# OxyBrain_V1_2.net
KiCad netlist of a schematic drawn in EAGLE
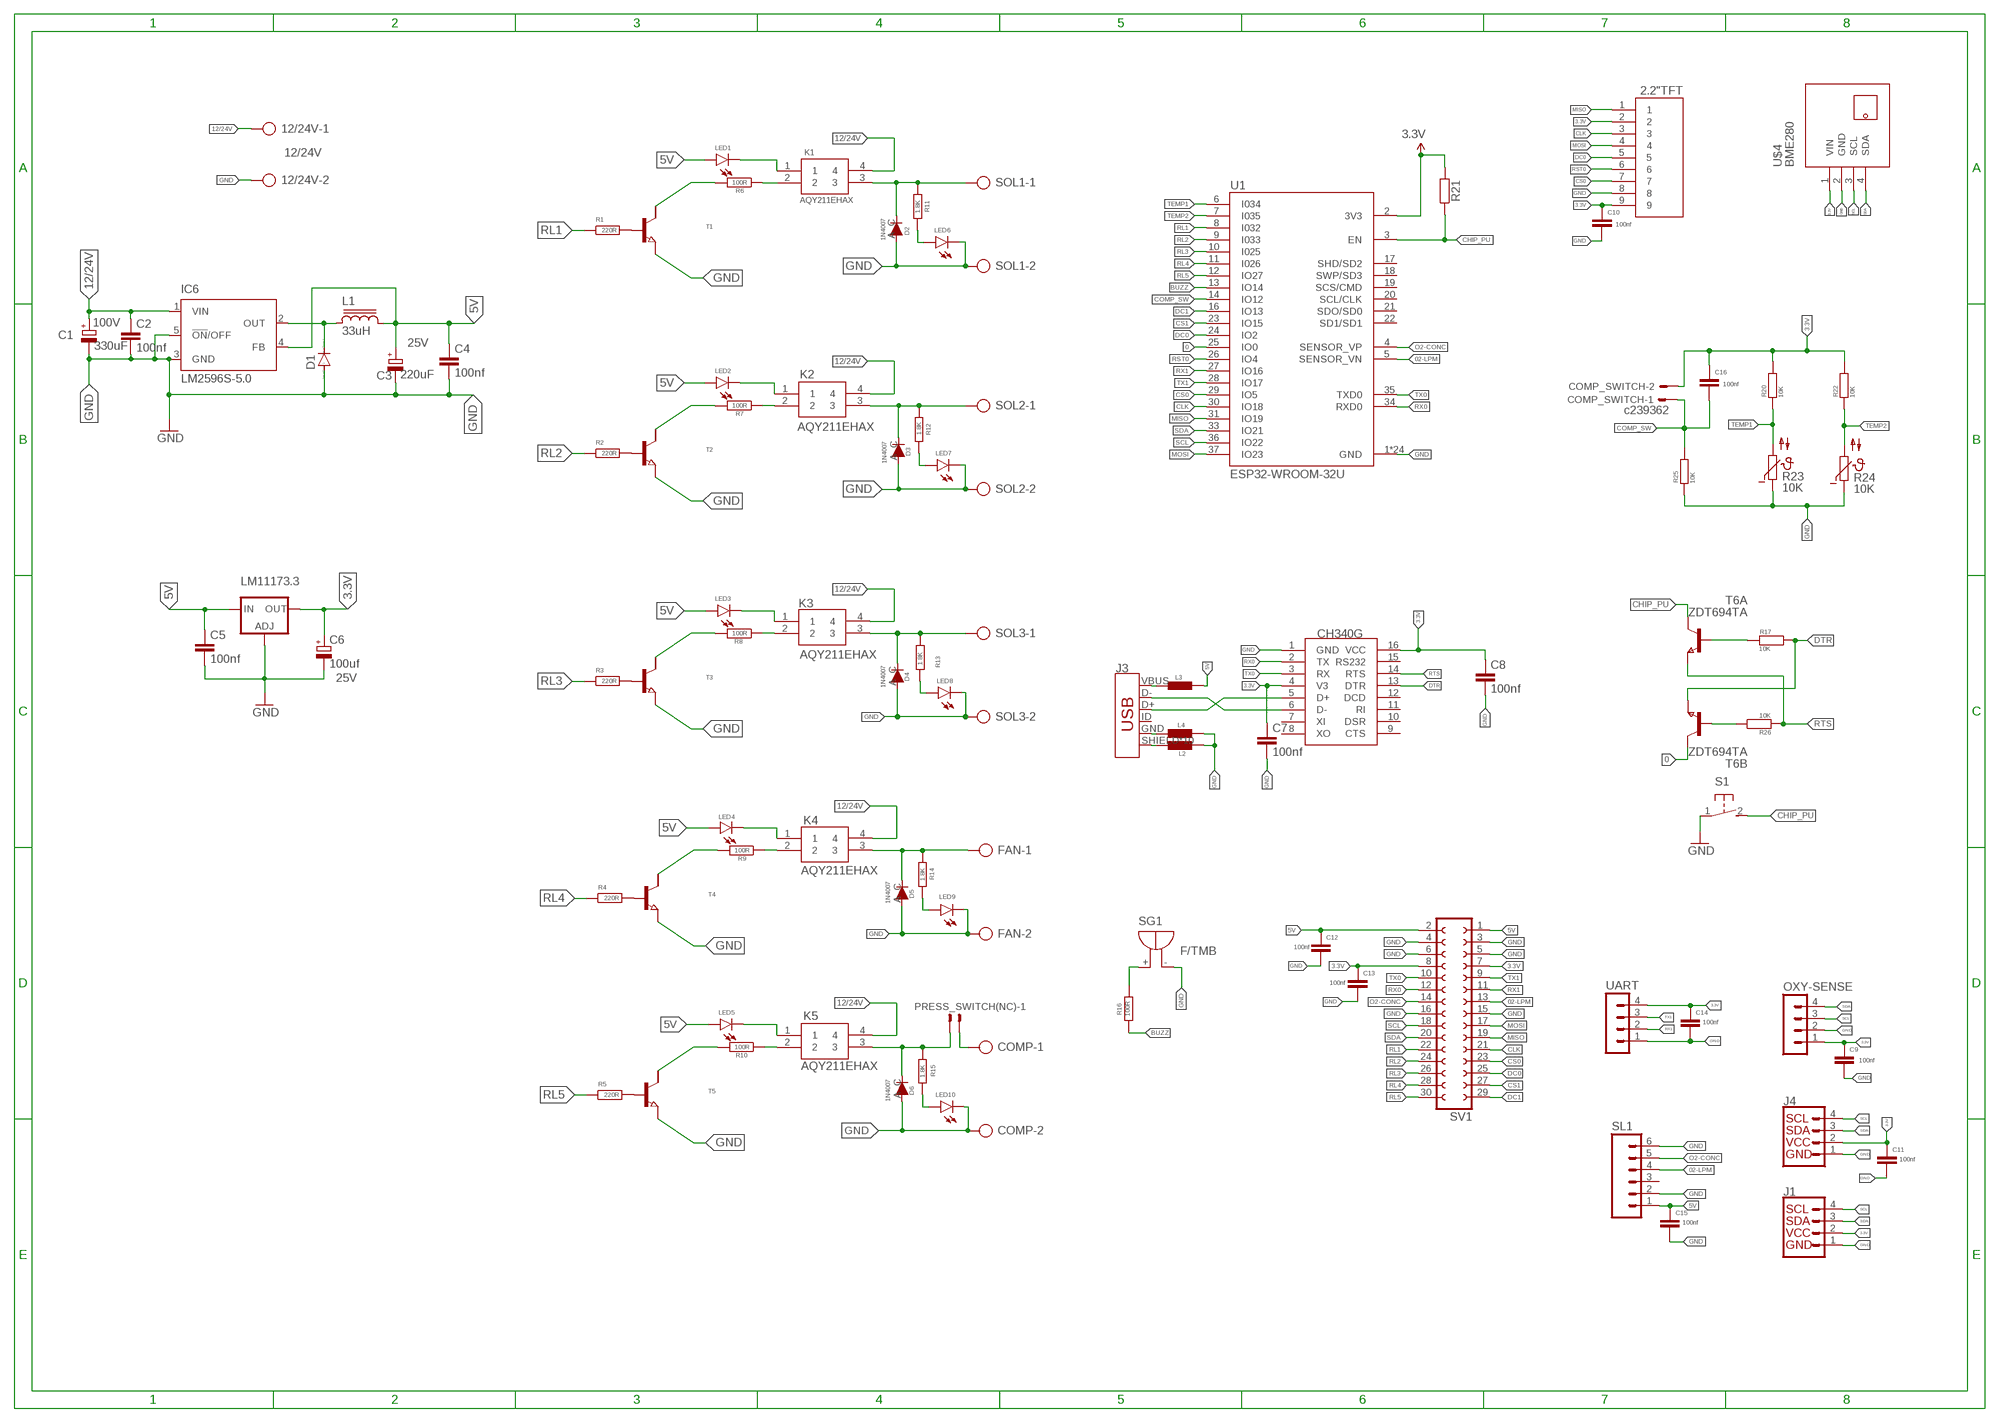
[diagram p0: schematic, sheet 1]

(export (version "E")
  (design (tool "Eeschema 10.0.6"))
  (components
    (comp (ref "2.2\"TFT")
      (value "1735446-9")
      (footprint "eagle-import:SHDR9W60P0X200_1X9_2000X520X63")
      (fields (field (name "MOUSER_PART_NUMBER") "571-1735446-9"))
      (libsource (lib "eagle-import") (part "1735446-9"))
    )
    (comp (ref "12/24V")
      (value "12/24V")
      (footprint "eagle-import:AK500_2")
      (libsource (lib "eagle-import") (part "AK500/2"))
    )
    (comp (ref "C1")
      (value "330uF")
      (footprint "eagle-import:140CLH-1010")
      (fields (field (name "VOLTAGE") "100V"))
      (libsource (lib "eagle-import") (part "CPOL-EU140CLH-1010"))
    )
    (comp (ref "C2")
      (value "100nf")
      (footprint "eagle-import:C1206")
      (libsource (lib "eagle-import") (part "C-EUC1206"))
    )
    (comp (ref "C3")
      (value "220uF")
      (footprint "eagle-import:153CLV-0605")
      (fields (field (name "VOLTAGE") "25V"))
      (libsource (lib "eagle-import") (part "CPOL-EU153CLV-0605"))
    )
    (comp (ref "C4")
      (value "100nf")
      (footprint "eagle-import:C1206")
      (libsource (lib "eagle-import") (part "C-EUC1206"))
    )
    (comp (ref "C5")
      (value "100nf")
      (footprint "eagle-import:C1206")
      (libsource (lib "eagle-import") (part "C-EUC1206"))
    )
    (comp (ref "C6")
      (value "100uf")
      (footprint "eagle-import:153CLV-0605")
      (fields (field (name "VOLTAGE") "25V"))
      (libsource (lib "eagle-import") (part "CPOL-EU153CLV-0605"))
    )
    (comp (ref "C7")
      (value "100nf")
      (footprint "eagle-import:C1206")
      (libsource (lib "eagle-import") (part "C-EUC1206"))
    )
    (comp (ref "C8")
      (value "100nf")
      (footprint "eagle-import:C1206")
      (libsource (lib "eagle-import") (part "C-EUC1206"))
    )
    (comp (ref "C9")
      (value "100nf")
      (footprint "eagle-import:C1206")
      (libsource (lib "eagle-import") (part "C-EUC1206"))
    )
    (comp (ref "C10")
      (value "100nf")
      (footprint "eagle-import:C1206")
      (libsource (lib "eagle-import") (part "C-EUC1206"))
    )
    (comp (ref "C11")
      (value "100nf")
      (footprint "eagle-import:C1206")
      (libsource (lib "eagle-import") (part "C-EUC1206"))
    )
    (comp (ref "C12")
      (value "100nf")
      (footprint "eagle-import:C1206")
      (libsource (lib "eagle-import") (part "C-EUC1206"))
    )
    (comp (ref "C13")
      (value "100nf")
      (footprint "eagle-import:C1206")
      (libsource (lib "eagle-import") (part "C-EUC1206"))
    )
    (comp (ref "C14")
      (value "100nf")
      (footprint "eagle-import:C1206")
      (libsource (lib "eagle-import") (part "C-EUC1206"))
    )
    (comp (ref "C15")
      (value "100nf")
      (footprint "eagle-import:C1206")
      (libsource (lib "eagle-import") (part "C-EUC1206"))
    )
    (comp (ref "C16")
      (value "100nf")
      (footprint "eagle-import:C1206")
      (libsource (lib "eagle-import") (part "C-EUC1206"))
    )
    (comp (ref "COMP")
      (value "AK500/2")
      (footprint "eagle-import:AK500_2")
      (libsource (lib "eagle-import") (part "AK500/2"))
    )
    (comp (ref "COMP_SWITCH")
      (value "c239362")
      (footprint "eagle-import:22-23-2021")
      (fields (field (name "MF") "MOLEX") (field (name "MPN") "22-23-2021"))
      (libsource (lib "eagle-import") (part "22-23-2021"))
    )
    (comp (ref "D1")
      (value "DIODE-SOD123")
      (footprint "eagle-import:SOD123")
      (libsource (lib "eagle-import") (part "DIODE-SOD123"))
    )
    (comp (ref "D2")
      (value "1N4007")
      (footprint "eagle-import:SOD-123FL")
      (libsource (lib "eagle-import") (part "1N4007_SMDSOD123-FL"))
    )
    (comp (ref "D3")
      (value "1N4007")
      (footprint "eagle-import:SOD-123FL")
      (libsource (lib "eagle-import") (part "1N4007_SMDSOD123-FL"))
    )
    (comp (ref "D4")
      (value "1N4007")
      (footprint "eagle-import:SOD-123FL")
      (libsource (lib "eagle-import") (part "1N4007_SMDSOD123-FL"))
    )
    (comp (ref "D5")
      (value "1N4007")
      (footprint "eagle-import:SOD-123FL")
      (libsource (lib "eagle-import") (part "1N4007_SMDSOD123-FL"))
    )
    (comp (ref "D6")
      (value "1N4007")
      (footprint "eagle-import:SOD-123FL")
      (libsource (lib "eagle-import") (part "1N4007_SMDSOD123-FL"))
    )
    (comp (ref "FAN")
      (value "AK500/2")
      (footprint "eagle-import:AK500_2")
      (libsource (lib "eagle-import") (part "AK500/2"))
    )
    (comp (ref "IC6")
      (value "LM2596S-5.0")
      (footprint "eagle-import:TO263-5")
      (fields (field (name "MF") "NATIONAL SEMICONDUCTOR") (field (name "MPN") "LM2596S-ADJ/NOPB"))
      (libsource (lib "eagle-import") (part "LM2596S"))
    )
    (comp (ref "J1")
      (value "I2C_STANDARD")
      (footprint "eagle-import:1X04")
      (libsource (lib "eagle-import") (part "I2C_STANDARD"))
    )
    (comp (ref "J3")
      (value "USB_MICRO-B_HALF_PTH_MILL")
      (footprint "eagle-import:USB-MICROB-PTH-MILL")
      (libsource (lib "eagle-import") (part "USB_MICRO-B_HALF_PTH_MILL"))
    )
    (comp (ref "J4")
      (value "I2C_STANDARD")
      (footprint "eagle-import:1X04")
      (libsource (lib "eagle-import") (part "I2C_STANDARD"))
    )
    (comp (ref "K1")
      (value "AQY211EHAX")
      (footprint "eagle-import:AQY21(SMD_DIP)")
      (fields (field (name "MOUSER_PART_NUMBER") "769-AQY211EHAX"))
      (libsource (lib "eagle-import") (part "AQY211EHAX"))
    )
    (comp (ref "K2")
      (value "AQY211EHAX")
      (footprint "eagle-import:AQY21(SMD_DIP)")
      (fields (field (name "MOUSER_PART_NUMBER") "769-AQY211EHAX"))
      (libsource (lib "eagle-import") (part "AQY211EHAX"))
    )
    (comp (ref "K3")
      (value "AQY211EHAX")
      (footprint "eagle-import:AQY21(SMD_DIP)")
      (fields (field (name "MOUSER_PART_NUMBER") "769-AQY211EHAX"))
      (libsource (lib "eagle-import") (part "AQY211EHAX"))
    )
    (comp (ref "K4")
      (value "AQY211EHAX")
      (footprint "eagle-import:AQY21(SMD_DIP)")
      (fields (field (name "MOUSER_PART_NUMBER") "769-AQY211EHAX"))
      (libsource (lib "eagle-import") (part "AQY211EHAX"))
    )
    (comp (ref "K5")
      (value "AQY211EHAX")
      (footprint "eagle-import:AQY21(SMD_DIP)")
      (fields (field (name "MOUSER_PART_NUMBER") "769-AQY211EHAX"))
      (libsource (lib "eagle-import") (part "AQY211EHAX"))
    )
    (comp (ref "L1")
      (value "33uH")
      (footprint "eagle-import:CDRH127_LD")
      (libsource (lib "eagle-import") (part "CDRH127/LD"))
    )
    (comp (ref "L2")
      (value "BLM15HD102SN1")
      (footprint "eagle-import:0402")
      (libsource (lib "eagle-import") (part "BLM15HD102SN1"))
    )
    (comp (ref "L3")
      (value "BLM15HD102SN1")
      (footprint "eagle-import:0402")
      (libsource (lib "eagle-import") (part "BLM15HD102SN1"))
    )
    (comp (ref "L4")
      (value "BLM15HD102SN1")
      (footprint "eagle-import:0402")
      (libsource (lib "eagle-import") (part "BLM15HD102SN1"))
    )
    (comp (ref "LED1")
      (value "LEDCHIPLED_1206")
      (footprint "eagle-import:CHIPLED_1206")
      (libsource (lib "eagle-import") (part "LEDCHIPLED_1206"))
    )
    (comp (ref "LED2")
      (value "LEDCHIPLED_1206")
      (footprint "eagle-import:CHIPLED_1206")
      (libsource (lib "eagle-import") (part "LEDCHIPLED_1206"))
    )
    (comp (ref "LED3")
      (value "LEDCHIPLED_1206")
      (footprint "eagle-import:CHIPLED_1206")
      (libsource (lib "eagle-import") (part "LEDCHIPLED_1206"))
    )
    (comp (ref "LED4")
      (value "LEDCHIPLED_1206")
      (footprint "eagle-import:CHIPLED_1206")
      (libsource (lib "eagle-import") (part "LEDCHIPLED_1206"))
    )
    (comp (ref "LED5")
      (value "LEDCHIPLED_1206")
      (footprint "eagle-import:CHIPLED_1206")
      (libsource (lib "eagle-import") (part "LEDCHIPLED_1206"))
    )
    (comp (ref "LED6")
      (value "LEDCHIPLED_1206")
      (footprint "eagle-import:CHIPLED_1206")
      (libsource (lib "eagle-import") (part "LEDCHIPLED_1206"))
    )
    (comp (ref "LED7")
      (value "LEDCHIPLED_1206")
      (footprint "eagle-import:CHIPLED_1206")
      (libsource (lib "eagle-import") (part "LEDCHIPLED_1206"))
    )
    (comp (ref "LED8")
      (value "LEDCHIPLED_1206")
      (footprint "eagle-import:CHIPLED_1206")
      (libsource (lib "eagle-import") (part "LEDCHIPLED_1206"))
    )
    (comp (ref "LED9")
      (value "LEDCHIPLED_1206")
      (footprint "eagle-import:CHIPLED_1206")
      (libsource (lib "eagle-import") (part "LEDCHIPLED_1206"))
    )
    (comp (ref "LED10")
      (value "LEDCHIPLED_1206")
      (footprint "eagle-import:CHIPLED_1206")
      (libsource (lib "eagle-import") (part "LEDCHIPLED_1206"))
    )
    (comp (ref "LM11173.3")
      (value "LD117ADT33TR")
      (footprint "eagle-import:DPACK")
      (libsource (lib "eagle-import") (part "LD117A?DT33TR"))
    )
    (comp (ref "OXY-SENSE")
      (value "MA04-1")
      (footprint "eagle-import:MA04-1")
      (libsource (lib "eagle-import") (part "MA04-1"))
    )
    (comp (ref "PRESS_SWITCH(NC)")
      (value "c239362")
      (footprint "eagle-import:22-23-2021")
      (fields (field (name "MF") "MOLEX") (field (name "MPN") "22-23-2021"))
      (libsource (lib "eagle-import") (part "22-23-2021"))
    )
    (comp (ref "R1")
      (value "220R")
      (footprint "eagle-import:M1206")
      (libsource (lib "eagle-import") (part "R-EU_M1206"))
    )
    (comp (ref "R2")
      (value "220R")
      (footprint "eagle-import:M1206")
      (libsource (lib "eagle-import") (part "R-EU_M1206"))
    )
    (comp (ref "R3")
      (value "220R")
      (footprint "eagle-import:M1206")
      (libsource (lib "eagle-import") (part "R-EU_M1206"))
    )
    (comp (ref "R4")
      (value "220R")
      (footprint "eagle-import:M1206")
      (libsource (lib "eagle-import") (part "R-EU_M1206"))
    )
    (comp (ref "R5")
      (value "220R")
      (footprint "eagle-import:M1206")
      (libsource (lib "eagle-import") (part "R-EU_M1206"))
    )
    (comp (ref "R6")
      (value "100R")
      (footprint "eagle-import:M1206")
      (libsource (lib "eagle-import") (part "R-EU_M1206"))
    )
    (comp (ref "R7")
      (value "100R")
      (footprint "eagle-import:M1206")
      (libsource (lib "eagle-import") (part "R-EU_M1206"))
    )
    (comp (ref "R8")
      (value "100R")
      (footprint "eagle-import:M1206")
      (libsource (lib "eagle-import") (part "R-EU_M1206"))
    )
    (comp (ref "R9")
      (value "100R")
      (footprint "eagle-import:M1206")
      (libsource (lib "eagle-import") (part "R-EU_M1206"))
    )
    (comp (ref "R10")
      (value "100R")
      (footprint "eagle-import:M1206")
      (libsource (lib "eagle-import") (part "R-EU_M1206"))
    )
    (comp (ref "R11")
      (value "1.8K")
      (footprint "eagle-import:M1206")
      (libsource (lib "eagle-import") (part "R-EU_M1206"))
    )
    (comp (ref "R12")
      (value "1.8K")
      (footprint "eagle-import:M1206")
      (libsource (lib "eagle-import") (part "R-EU_M1206"))
    )
    (comp (ref "R13")
      (value "1.8K")
      (footprint "eagle-import:M1206")
      (libsource (lib "eagle-import") (part "R-EU_M1206"))
    )
    (comp (ref "R14")
      (value "1.8K")
      (footprint "eagle-import:M1206")
      (libsource (lib "eagle-import") (part "R-EU_M1206"))
    )
    (comp (ref "R15")
      (value "1.8K")
      (footprint "eagle-import:M1206")
      (libsource (lib "eagle-import") (part "R-EU_M1206"))
    )
    (comp (ref "R16")
      (value "100R")
      (footprint "eagle-import:M1206")
      (libsource (lib "eagle-import") (part "R-EU_M1206"))
    )
    (comp (ref "R17")
      (value "10K")
      (footprint "eagle-import:M1206")
      (libsource (lib "eagle-import") (part "R-EU_M1206"))
    )
    (comp (ref "R20")
      (value "10K")
      (footprint "eagle-import:M1206")
      (libsource (lib "eagle-import") (part "R-EU_M1206"))
    )
    (comp (ref "R21")
      (value "10k")
      (footprint "eagle-import:M1206")
      (libsource (lib "eagle-import") (part "R-EU_M1206"))
    )
    (comp (ref "R22")
      (value "10K")
      (footprint "eagle-import:M1206")
      (libsource (lib "eagle-import") (part "R-EU_M1206"))
    )
    (comp (ref "R23")
      (value "10K")
      (footprint "eagle-import:P640")
      (libsource (lib "eagle-import") (part "NTC640"))
    )
    (comp (ref "R24")
      (value "10K")
      (footprint "eagle-import:P640")
      (libsource (lib "eagle-import") (part "NTC640"))
    )
    (comp (ref "R25")
      (value "10K")
      (footprint "eagle-import:M1206")
      (libsource (lib "eagle-import") (part "R-EU_M1206"))
    )
    (comp (ref "R26")
      (value "10K")
      (footprint "eagle-import:M1206")
      (libsource (lib "eagle-import") (part "R-EU_M1206"))
    )
    (comp (ref "S1")
      (value "B3U-1000P(M)-B")
      (footprint "eagle-import:DTSM-3")
      (libsource (lib "eagle-import") (part "DTSM-3"))
    )
    (comp (ref "SG1")
      (value "F/TMB")
      (footprint "eagle-import:F_TMB")
      (libsource (lib "eagle-import") (part "F/TMB"))
    )
    (comp (ref "SL1")
      (value "M06")
      (footprint "eagle-import:06P")
      (libsource (lib "eagle-import") (part "M06"))
    )
    (comp (ref "SOL1")
      (value "AK500/2")
      (footprint "eagle-import:AK500_2")
      (libsource (lib "eagle-import") (part "AK500/2"))
    )
    (comp (ref "SOL2")
      (value "AK500/2")
      (footprint "eagle-import:AK500_2")
      (libsource (lib "eagle-import") (part "AK500/2"))
    )
    (comp (ref "SOL3")
      (value "AK500/2")
      (footprint "eagle-import:AK500_2")
      (libsource (lib "eagle-import") (part "AK500/2"))
    )
    (comp (ref "SV1")
      (value "FE15-2")
      (footprint "eagle-import:FE15-2")
      (libsource (lib "eagle-import") (part "FE15-2"))
    )
    (comp (ref "T1")
      (value "600mA/40V")
      (footprint "eagle-import:SOT89")
      (libsource (lib "eagle-import") (part "NPN-TRANSISTIOR-2COLSOT89"))
    )
    (comp (ref "T2")
      (value "600mA/40V")
      (footprint "eagle-import:SOT89")
      (libsource (lib "eagle-import") (part "NPN-TRANSISTIOR-2COLSOT89"))
    )
    (comp (ref "T3")
      (value "600mA/40V")
      (footprint "eagle-import:SOT89")
      (libsource (lib "eagle-import") (part "NPN-TRANSISTIOR-2COLSOT89"))
    )
    (comp (ref "T4")
      (value "600mA/40V")
      (footprint "eagle-import:SOT89")
      (libsource (lib "eagle-import") (part "NPN-TRANSISTIOR-2COLSOT89"))
    )
    (comp (ref "T5")
      (value "600mA/40V")
      (footprint "eagle-import:SOT89")
      (libsource (lib "eagle-import") (part "NPN-TRANSISTIOR-2COLSOT89"))
    )
    (comp (ref "T6")
      (value "ZDT694TA")
      (footprint "eagle-import:SM8")
      (libsource (lib "eagle-import") (part "NPN2SM8"))
    )
    (comp (ref "U$1")
      (value "CH340G")
      (footprint "eagle-import:SOIC16")
      (libsource (lib "eagle-import") (part "CH340G"))
    )
    (comp (ref "U$4")
      (value "BME280")
      (footprint "eagle-import:TEMP-HUM-PRES-BME280")
      (libsource (lib "eagle-import") (part "TEMP-HUM-PRES-BME280"))
    )
    (comp (ref "U1")
      (value "ESP32-WROOM-32U")
      (footprint "eagle-import:XCVR_ESP32-WROOM-32U")
      (fields (field (name "MF") "Espressif Systems"))
      (libsource (lib "eagle-import") (part "ESP32-WROOM-32U"))
    )
    (comp (ref "UART")
      (value "MA04-1")
      (footprint "eagle-import:MA04-1")
      (libsource (lib "eagle-import") (part "MA04-1"))
    )
  )
  (nets
    (net (code "1") (name "0") (class "Default")
      (node (ref "T6") (pin "7") (pinfunction "C_7") (pintype "passive"))
      (node (ref "T6") (pin "8") (pinfunction "C_8") (pintype "passive"))
      (node (ref "U1") (pin "25") (pinfunction "IO0_25") (pintype "bidirectional"))
    )
    (net (code "2") (name "02-LPM") (class "Default")
      (node (ref "SL1") (pin "4") (pinfunction "4_4") (pintype "passive"))
      (node (ref "SV1") (pin "13") (pinfunction "13_13") (pintype "passive"))
      (node (ref "U1") (pin "5") (pinfunction "SENSOR_VN_5") (pintype "input"))
    )
    (net (code "3") (name "3.3V") (class "Default")
      (node (ref "2.2\"TFT") (pin "2") (pinfunction "2_2") (pintype "bidirectional"))
      (node (ref "2.2\"TFT") (pin "9") (pinfunction "9_9") (pintype "bidirectional"))
      (node (ref "C10") (pin "1") (pinfunction "1_1") (pintype "passive"))
      (node (ref "C11") (pin "1") (pinfunction "1_1") (pintype "passive"))
      (node (ref "C13") (pin "1") (pinfunction "1_1") (pintype "passive"))
      (node (ref "C14") (pin "1") (pinfunction "1_1") (pintype "passive"))
      (node (ref "C16") (pin "1") (pinfunction "1_1") (pintype "passive"))
      (node (ref "C6") (pin "+") (pinfunction "+_+") (pintype "passive"))
      (node (ref "C7") (pin "1") (pinfunction "1_1") (pintype "passive"))
      (node (ref "C8") (pin "1") (pinfunction "1_1") (pintype "passive"))
      (node (ref "C9") (pin "1") (pinfunction "1_1") (pintype "passive"))
      (node (ref "COMP_SWITCH") (pin "2") (pinfunction "S_2") (pintype "passive"))
      (node (ref "J1") (pin "2") (pinfunction "2_2") (pintype "power_in"))
      (node (ref "J4") (pin "2") (pinfunction "2_2") (pintype "power_in"))
      (node (ref "LM11173.3") (pin "4") (pinfunction "OUT_4") (pintype "passive"))
      (node (ref "OXY-SENSE") (pin "1") (pinfunction "1_1") (pintype "passive"))
      (node (ref "R20") (pin "1") (pinfunction "1_1") (pintype "passive"))
      (node (ref "R21") (pin "2") (pinfunction "2_2") (pintype "passive"))
      (node (ref "R22") (pin "1") (pinfunction "1_1") (pintype "passive"))
      (node (ref "SV1") (pin "7") (pinfunction "7_7") (pintype "passive"))
      (node (ref "SV1") (pin "8") (pinfunction "8_8") (pintype "passive"))
      (node (ref "U$1") (pin "16") (pinfunction "VCC_16") (pintype "bidirectional"))
      (node (ref "U$1") (pin "4") (pinfunction "V3_4") (pintype "bidirectional"))
      (node (ref "U$4") (pin "1") (pinfunction "VIN_1") (pintype "power_in"))
      (node (ref "U1") (pin "2") (pinfunction "3V3_2") (pintype "power_in"))
      (node (ref "UART") (pin "4") (pinfunction "4_4") (pintype "passive"))
    )
    (net (code "4") (name "5V") (class "Default")
      (node (ref "C12") (pin "1") (pinfunction "1_1") (pintype "passive"))
      (node (ref "C15") (pin "1") (pinfunction "1_1") (pintype "passive"))
      (node (ref "C3") (pin "+") (pinfunction "+_+") (pintype "passive"))
      (node (ref "C4") (pin "1") (pinfunction "1_1") (pintype "passive"))
      (node (ref "C5") (pin "1") (pinfunction "1_1") (pintype "passive"))
      (node (ref "IC6") (pin "4") (pinfunction "FB_4") (pintype "input"))
      (node (ref "L1") (pin "2") (pinfunction "2_2") (pintype "passive"))
      (node (ref "L3") (pin "2") (pinfunction "2_2") (pintype "passive"))
      (node (ref "LED1") (pin "A") (pinfunction "A_A") (pintype "passive"))
      (node (ref "LED2") (pin "A") (pinfunction "A_A") (pintype "passive"))
      (node (ref "LED3") (pin "A") (pinfunction "A_A") (pintype "passive"))
      (node (ref "LED4") (pin "A") (pinfunction "A_A") (pintype "passive"))
      (node (ref "LED5") (pin "A") (pinfunction "A_A") (pintype "passive"))
      (node (ref "LM11173.3") (pin "3") (pinfunction "IN_3") (pintype "input"))
      (node (ref "SL1") (pin "1") (pinfunction "1_1") (pintype "passive"))
      (node (ref "SV1") (pin "1") (pinfunction "1_1") (pintype "passive"))
      (node (ref "SV1") (pin "2") (pinfunction "2_2") (pintype "passive"))
    )
    (net (code "5") (name "12{slash}24V") (class "Default")
      (node (ref "12/24V") (pin "1") (pinfunction "KL_1") (pintype "passive"))
      (node (ref "C1") (pin "+") (pinfunction "+_+") (pintype "passive"))
      (node (ref "C2") (pin "1") (pinfunction "1_1") (pintype "passive"))
      (node (ref "IC6") (pin "1") (pinfunction "VIN_1") (pintype "input"))
      (node (ref "K1") (pin "4") (pinfunction "4_4") (pintype "bidirectional"))
      (node (ref "K2") (pin "4") (pinfunction "4_4") (pintype "bidirectional"))
      (node (ref "K3") (pin "4") (pinfunction "4_4") (pintype "bidirectional"))
      (node (ref "K4") (pin "4") (pinfunction "4_4") (pintype "bidirectional"))
      (node (ref "K5") (pin "4") (pinfunction "4_4") (pintype "bidirectional"))
    )
    (net (code "6") (name "BUZZ") (class "Default")
      (node (ref "R16") (pin "1") (pinfunction "1_1") (pintype "passive"))
      (node (ref "U1") (pin "13") (pinfunction "IO14_13") (pintype "bidirectional"))
    )
    (net (code "7") (name "CHIP_PU") (class "Default")
      (node (ref "R21") (pin "1") (pinfunction "1_1") (pintype "passive"))
      (node (ref "S1") (pin "2") (pinfunction "2_2") (pintype "passive"))
      (node (ref "T6") (pin "5") (pinfunction "C_5") (pintype "passive"))
      (node (ref "T6") (pin "6") (pinfunction "C_6") (pintype "passive"))
      (node (ref "U1") (pin "3") (pinfunction "EN_3") (pintype "input"))
    )
    (net (code "8") (name "CLK") (class "Default")
      (node (ref "2.2\"TFT") (pin "3") (pinfunction "3_3") (pintype "bidirectional"))
      (node (ref "SV1") (pin "21") (pinfunction "21_21") (pintype "passive"))
      (node (ref "U1") (pin "30") (pinfunction "IO18_30") (pintype "bidirectional"))
    )
    (net (code "9") (name "COMP_SW") (class "Default")
      (node (ref "C16") (pin "2") (pinfunction "2_2") (pintype "passive"))
      (node (ref "COMP_SWITCH") (pin "1") (pinfunction "S_1") (pintype "passive"))
      (node (ref "R25") (pin "1") (pinfunction "1_1") (pintype "passive"))
      (node (ref "U1") (pin "14") (pinfunction "IO12_14") (pintype "bidirectional"))
    )
    (net (code "10") (name "CS0") (class "Default")
      (node (ref "2.2\"TFT") (pin "7") (pinfunction "7_7") (pintype "bidirectional"))
      (node (ref "SV1") (pin "23") (pinfunction "23_23") (pintype "passive"))
      (node (ref "U1") (pin "29") (pinfunction "IO5_29") (pintype "bidirectional"))
    )
    (net (code "11") (name "CS1") (class "Default")
      (node (ref "SV1") (pin "27") (pinfunction "27_27") (pintype "passive"))
      (node (ref "U1") (pin "23") (pinfunction "IO15_23") (pintype "bidirectional"))
    )
    (net (code "12") (name "DC0") (class "Default")
      (node (ref "2.2\"TFT") (pin "5") (pinfunction "5_5") (pintype "bidirectional"))
      (node (ref "SV1") (pin "25") (pinfunction "25_25") (pintype "passive"))
      (node (ref "U1") (pin "24") (pinfunction "IO2_24") (pintype "bidirectional"))
    )
    (net (code "13") (name "DC1") (class "Default")
      (node (ref "SV1") (pin "29") (pinfunction "29_29") (pintype "passive"))
      (node (ref "U1") (pin "16") (pinfunction "IO13_16") (pintype "bidirectional"))
    )
    (net (code "14") (name "DTR") (class "Default")
      (node (ref "R17") (pin "1") (pinfunction "1_1") (pintype "passive"))
      (node (ref "T6") (pin "1") (pinfunction "E_1") (pintype "passive"))
      (node (ref "U$1") (pin "13") (pinfunction "DTR_13") (pintype "bidirectional"))
    )
    (net (code "15") (name "GND") (class "Default")
      (node (ref "12/24V") (pin "2") (pinfunction "KL_2") (pintype "passive"))
      (node (ref "2.2\"TFT") (pin "8") (pinfunction "8_8") (pintype "bidirectional"))
      (node (ref "C1") (pin "-") (pinfunction "-_-") (pintype "passive"))
      (node (ref "C10") (pin "2") (pinfunction "2_2") (pintype "passive"))
      (node (ref "C11") (pin "2") (pinfunction "2_2") (pintype "passive"))
      (node (ref "C12") (pin "2") (pinfunction "2_2") (pintype "passive"))
      (node (ref "C13") (pin "2") (pinfunction "2_2") (pintype "passive"))
      (node (ref "C14") (pin "2") (pinfunction "2_2") (pintype "passive"))
      (node (ref "C15") (pin "2") (pinfunction "2_2") (pintype "passive"))
      (node (ref "C2") (pin "2") (pinfunction "2_2") (pintype "passive"))
      (node (ref "C3") (pin "-") (pinfunction "-_-") (pintype "passive"))
      (node (ref "C4") (pin "2") (pinfunction "2_2") (pintype "passive"))
      (node (ref "C5") (pin "2") (pinfunction "2_2") (pintype "passive"))
      (node (ref "C6") (pin "-") (pinfunction "-_-") (pintype "passive"))
      (node (ref "C7") (pin "2") (pinfunction "2_2") (pintype "passive"))
      (node (ref "C8") (pin "2") (pinfunction "2_2") (pintype "passive"))
      (node (ref "C9") (pin "2") (pinfunction "2_2") (pintype "passive"))
      (node (ref "COMP") (pin "2") (pinfunction "KL_2") (pintype "passive"))
      (node (ref "D1") (pin "A") (pinfunction "A_A") (pintype "passive"))
      (node (ref "D2") (pin "A") (pinfunction "A_A") (pintype "bidirectional"))
      (node (ref "D3") (pin "A") (pinfunction "A_A") (pintype "bidirectional"))
      (node (ref "D4") (pin "A") (pinfunction "A_A") (pintype "bidirectional"))
      (node (ref "D5") (pin "A") (pinfunction "A_A") (pintype "bidirectional"))
      (node (ref "D6") (pin "A") (pinfunction "A_A") (pintype "bidirectional"))
      (node (ref "FAN") (pin "2") (pinfunction "KL_2") (pintype "passive"))
      (node (ref "IC6") (pin "3") (pinfunction "GND_3") (pintype "power_in"))
      (node (ref "IC6") (pin "5") (pinfunction "~{ON}/OFF_5") (pintype "input"))
      (node (ref "J1") (pin "1") (pinfunction "1_1") (pintype "power_in"))
      (node (ref "J4") (pin "1") (pinfunction "1_1") (pintype "power_in"))
      (node (ref "L2") (pin "2") (pinfunction "2_2") (pintype "passive"))
      (node (ref "L4") (pin "2") (pinfunction "2_2") (pintype "passive"))
      (node (ref "LED10") (pin "C") (pinfunction "C_C") (pintype "passive"))
      (node (ref "LED6") (pin "C") (pinfunction "C_C") (pintype "passive"))
      (node (ref "LED7") (pin "C") (pinfunction "C_C") (pintype "passive"))
      (node (ref "LED8") (pin "C") (pinfunction "C_C") (pintype "passive"))
      (node (ref "LED9") (pin "C") (pinfunction "C_C") (pintype "passive"))
      (node (ref "LM11173.3") (pin "1") (pinfunction "ADJ_1") (pintype "input"))
      (node (ref "OXY-SENSE") (pin "2") (pinfunction "2_2") (pintype "passive"))
      (node (ref "R23") (pin "1") (pinfunction "1_1") (pintype "passive"))
      (node (ref "R24") (pin "1") (pinfunction "1_1") (pintype "passive"))
      (node (ref "R25") (pin "2") (pinfunction "2_2") (pintype "passive"))
      (node (ref "S1") (pin "1") (pinfunction "1_1") (pintype "passive"))
      (node (ref "SG1") (pin "-") (pinfunction "-_-") (pintype "passive"))
      (node (ref "SL1") (pin "2") (pinfunction "2_2") (pintype "passive"))
      (node (ref "SL1") (pin "6") (pinfunction "6_6") (pintype "passive"))
      (node (ref "SOL1") (pin "2") (pinfunction "KL_2") (pintype "passive"))
      (node (ref "SOL2") (pin "2") (pinfunction "KL_2") (pintype "passive"))
      (node (ref "SOL3") (pin "2") (pinfunction "KL_2") (pintype "passive"))
      (node (ref "SV1") (pin "15") (pinfunction "15_15") (pintype "passive"))
      (node (ref "SV1") (pin "16") (pinfunction "16_16") (pintype "passive"))
      (node (ref "SV1") (pin "3") (pinfunction "3_3") (pintype "passive"))
      (node (ref "SV1") (pin "4") (pinfunction "4_4") (pintype "passive"))
      (node (ref "SV1") (pin "5") (pinfunction "5_5") (pintype "passive"))
      (node (ref "SV1") (pin "6") (pinfunction "6_6") (pintype "passive"))
      (node (ref "T1") (pin "3") (pinfunction "E_3") (pintype "passive"))
      (node (ref "T2") (pin "3") (pinfunction "E_3") (pintype "passive"))
      (node (ref "T3") (pin "3") (pinfunction "E_3") (pintype "passive"))
      (node (ref "T4") (pin "3") (pinfunction "E_3") (pintype "passive"))
      (node (ref "T5") (pin "3") (pinfunction "E_3") (pintype "passive"))
      (node (ref "U$1") (pin "1") (pinfunction "GND_1") (pintype "bidirectional"))
      (node (ref "U$4") (pin "2") (pinfunction "GND_2") (pintype "power_in"))
      (node (ref "U1") (pin "1") (pinfunction "GND_1") (pintype "power_in"))
      (node (ref "U1") (pin "15") (pinfunction "GND_15") (pintype "power_in"))
      (node (ref "U1") (pin "38") (pinfunction "GND_38") (pintype "power_in"))
      (node (ref "U1") (pin "G.1") (pinfunction "GND_G.1") (pintype "power_in"))
      (node (ref "U1") (pin "G.10") (pinfunction "GND_G.10") (pintype "power_in"))
      (node (ref "U1") (pin "G.11") (pinfunction "GND_G.11") (pintype "power_in"))
      (node (ref "U1") (pin "G.12") (pinfunction "GND_G.12") (pintype "power_in"))
      (node (ref "U1") (pin "G.13") (pinfunction "GND_G.13") (pintype "power_in"))
      (node (ref "U1") (pin "G.14") (pinfunction "GND_G.14") (pintype "power_in"))
      (node (ref "U1") (pin "G.15") (pinfunction "GND_G.15") (pintype "power_in"))
      (node (ref "U1") (pin "G.16") (pinfunction "GND_G.16") (pintype "power_in"))
      (node (ref "U1") (pin "G.17") (pinfunction "GND_G.17") (pintype "power_in"))
      (node (ref "U1") (pin "G.18") (pinfunction "GND_G.18") (pintype "power_in"))
      (node (ref "U1") (pin "G.19") (pinfunction "GND_G.19") (pintype "power_in"))
      (node (ref "U1") (pin "G.2") (pinfunction "GND_G.2") (pintype "power_in"))
      (node (ref "U1") (pin "G.20") (pinfunction "GND_G.20") (pintype "power_in"))
      (node (ref "U1") (pin "G.21") (pinfunction "GND_G.21") (pintype "power_in"))
      (node (ref "U1") (pin "G.22") (pinfunction "GND_G.22") (pintype "power_in"))
      (node (ref "U1") (pin "G.4") (pinfunction "GND_G.4") (pintype "power_in"))
      (node (ref "U1") (pin "G.5") (pinfunction "GND_G.5") (pintype "power_in"))
      (node (ref "U1") (pin "G.6") (pinfunction "GND_G.6") (pintype "power_in"))
      (node (ref "U1") (pin "G.7") (pinfunction "GND_G.7") (pintype "power_in"))
      (node (ref "U1") (pin "G.8") (pinfunction "GND_G.8") (pintype "power_in"))
      (node (ref "U1") (pin "G.9") (pinfunction "GND_G.9") (pintype "power_in"))
      (node (ref "UART") (pin "1") (pinfunction "1_1") (pintype "passive"))
    )
    (net (code "16") (name "MISO") (class "Default")
      (node (ref "2.2\"TFT") (pin "1") (pinfunction "1_1") (pintype "bidirectional"))
      (node (ref "SV1") (pin "19") (pinfunction "19_19") (pintype "passive"))
      (node (ref "U1") (pin "31") (pinfunction "IO19_31") (pintype "bidirectional"))
    )
    (net (code "17") (name "MOSI") (class "Default")
      (node (ref "2.2\"TFT") (pin "4") (pinfunction "4_4") (pintype "bidirectional"))
      (node (ref "SV1") (pin "17") (pinfunction "17_17") (pintype "passive"))
      (node (ref "U1") (pin "37") (pinfunction "IO23_37") (pintype "bidirectional"))
    )
    (net (code "18") (name "Net-(COMPA-KL)") (class "Default")
      (node (ref "COMP") (pin "1") (pinfunction "KL_1") (pintype "passive"))
      (node (ref "PRESS_SWITCH(NC)") (pin "2") (pinfunction "S_2") (pintype "passive"))
    )
    (net (code "19") (name "Net-(D2-K)") (class "Default")
      (node (ref "D2") (pin "C") (pinfunction "K_C") (pintype "bidirectional"))
      (node (ref "K1") (pin "3") (pinfunction "3_3") (pintype "bidirectional"))
      (node (ref "R11") (pin "1") (pinfunction "1_1") (pintype "passive"))
      (node (ref "SOL1") (pin "1") (pinfunction "KL_1") (pintype "passive"))
    )
    (net (code "20") (name "Net-(D3-K)") (class "Default")
      (node (ref "D3") (pin "C") (pinfunction "K_C") (pintype "bidirectional"))
      (node (ref "K2") (pin "3") (pinfunction "3_3") (pintype "bidirectional"))
      (node (ref "R12") (pin "1") (pinfunction "1_1") (pintype "passive"))
      (node (ref "SOL2") (pin "1") (pinfunction "KL_1") (pintype "passive"))
    )
    (net (code "21") (name "Net-(D4-K)") (class "Default")
      (node (ref "D4") (pin "C") (pinfunction "K_C") (pintype "bidirectional"))
      (node (ref "K3") (pin "3") (pinfunction "3_3") (pintype "bidirectional"))
      (node (ref "R13") (pin "1") (pinfunction "1_1") (pintype "passive"))
      (node (ref "SOL3") (pin "1") (pinfunction "KL_1") (pintype "passive"))
    )
    (net (code "22") (name "Net-(D5-K)") (class "Default")
      (node (ref "D5") (pin "C") (pinfunction "K_C") (pintype "bidirectional"))
      (node (ref "FAN") (pin "1") (pinfunction "KL_1") (pintype "passive"))
      (node (ref "K4") (pin "3") (pinfunction "3_3") (pintype "bidirectional"))
      (node (ref "R14") (pin "1") (pinfunction "1_1") (pintype "passive"))
    )
    (net (code "23") (name "Net-(D6-K)") (class "Default")
      (node (ref "D6") (pin "C") (pinfunction "K_C") (pintype "bidirectional"))
      (node (ref "K5") (pin "3") (pinfunction "3_3") (pintype "bidirectional"))
      (node (ref "PRESS_SWITCH(NC)") (pin "1") (pinfunction "S_1") (pintype "passive"))
      (node (ref "R15") (pin "1") (pinfunction "1_1") (pintype "passive"))
    )
    (net (code "24") (name "Net-(IC6-OUT)") (class "Default")
      (node (ref "D1") (pin "C") (pinfunction "C_C") (pintype "passive"))
      (node (ref "IC6") (pin "2") (pinfunction "OUT_2") (pintype "output"))
      (node (ref "L1") (pin "1") (pinfunction "1_1") (pintype "passive"))
    )
    (net (code "25") (name "Net-(J3-PadGND)") (class "Default")
      (node (ref "J3") (pin "GND") (pinfunction "GND_GND") (pintype "power_in"))
      (node (ref "L4") (pin "1") (pinfunction "1_1") (pintype "passive"))
    )
    (net (code "26") (name "Net-(J3-PadSHIELD)") (class "Default")
      (node (ref "J3") (pin "SHIELD") (pinfunction "SHIELD_SHIELD") (pintype "bidirectional"))
      (node (ref "J3") (pin "SHIELD10") (pinfunction "SHIELD_SHIELD10") (pintype "bidirectional"))
      (node (ref "J3") (pin "SHIELD2") (pinfunction "SHIELD_SHIELD2") (pintype "bidirectional"))
      (node (ref "J3") (pin "SHIELD3") (pinfunction "SHIELD_SHIELD3") (pintype "bidirectional"))
      (node (ref "J3") (pin "SHIELD4") (pinfunction "SHIELD_SHIELD4") (pintype "bidirectional"))
      (node (ref "J3") (pin "SHIELD5") (pinfunction "SHIELD_SHIELD5") (pintype "bidirectional"))
      (node (ref "J3") (pin "SHIELD6") (pinfunction "SHIELD_SHIELD6") (pintype "bidirectional"))
      (node (ref "J3") (pin "SHIELD7") (pinfunction "SHIELD_SHIELD7") (pintype "bidirectional"))
      (node (ref "J3") (pin "SHIELD8") (pinfunction "SHIELD_SHIELD8") (pintype "bidirectional"))
      (node (ref "J3") (pin "SHIELD9") (pinfunction "SHIELD_SHIELD9") (pintype "bidirectional"))
      (node (ref "L2") (pin "1") (pinfunction "1_1") (pintype "passive"))
    )
    (net (code "27") (name "Net-(J3-PadVBUS)") (class "Default")
      (node (ref "J3") (pin "VBUS") (pinfunction "VBUS_VBUS") (pintype "power_in"))
      (node (ref "L3") (pin "1") (pinfunction "1_1") (pintype "passive"))
    )
    (net (code "28") (name "Net-(K1-Pad1)") (class "Default")
      (node (ref "K1") (pin "1") (pinfunction "1_1") (pintype "bidirectional"))
      (node (ref "LED1") (pin "C") (pinfunction "C_C") (pintype "passive"))
    )
    (net (code "29") (name "Net-(K1-Pad2)") (class "Default")
      (node (ref "K1") (pin "2") (pinfunction "2_2") (pintype "bidirectional"))
      (node (ref "R6") (pin "1") (pinfunction "1_1") (pintype "passive"))
    )
    (net (code "30") (name "Net-(K2-Pad1)") (class "Default")
      (node (ref "K2") (pin "1") (pinfunction "1_1") (pintype "bidirectional"))
      (node (ref "LED2") (pin "C") (pinfunction "C_C") (pintype "passive"))
    )
    (net (code "31") (name "Net-(K2-Pad2)") (class "Default")
      (node (ref "K2") (pin "2") (pinfunction "2_2") (pintype "bidirectional"))
      (node (ref "R7") (pin "1") (pinfunction "1_1") (pintype "passive"))
    )
    (net (code "32") (name "Net-(K3-Pad1)") (class "Default")
      (node (ref "K3") (pin "1") (pinfunction "1_1") (pintype "bidirectional"))
      (node (ref "LED3") (pin "C") (pinfunction "C_C") (pintype "passive"))
    )
    (net (code "33") (name "Net-(K3-Pad2)") (class "Default")
      (node (ref "K3") (pin "2") (pinfunction "2_2") (pintype "bidirectional"))
      (node (ref "R8") (pin "1") (pinfunction "1_1") (pintype "passive"))
    )
    (net (code "34") (name "Net-(K4-Pad1)") (class "Default")
      (node (ref "K4") (pin "1") (pinfunction "1_1") (pintype "bidirectional"))
      (node (ref "LED4") (pin "C") (pinfunction "C_C") (pintype "passive"))
    )
    (net (code "35") (name "Net-(K4-Pad2)") (class "Default")
      (node (ref "K4") (pin "2") (pinfunction "2_2") (pintype "bidirectional"))
      (node (ref "R9") (pin "1") (pinfunction "1_1") (pintype "passive"))
    )
    (net (code "36") (name "Net-(K5-Pad1)") (class "Default")
      (node (ref "K5") (pin "1") (pinfunction "1_1") (pintype "bidirectional"))
      (node (ref "LED5") (pin "C") (pinfunction "C_C") (pintype "passive"))
    )
    (net (code "37") (name "Net-(K5-Pad2)") (class "Default")
      (node (ref "K5") (pin "2") (pinfunction "2_2") (pintype "bidirectional"))
      (node (ref "R10") (pin "1") (pinfunction "1_1") (pintype "passive"))
    )
    (net (code "38") (name "Net-(LED6-PadA)") (class "Default")
      (node (ref "LED6") (pin "A") (pinfunction "A_A") (pintype "passive"))
      (node (ref "R11") (pin "2") (pinfunction "2_2") (pintype "passive"))
    )
    (net (code "39") (name "Net-(LED7-PadA)") (class "Default")
      (node (ref "LED7") (pin "A") (pinfunction "A_A") (pintype "passive"))
      (node (ref "R12") (pin "2") (pinfunction "2_2") (pintype "passive"))
    )
    (net (code "40") (name "Net-(LED8-PadA)") (class "Default")
      (node (ref "LED8") (pin "A") (pinfunction "A_A") (pintype "passive"))
      (node (ref "R13") (pin "2") (pinfunction "2_2") (pintype "passive"))
    )
    (net (code "41") (name "Net-(LED9-PadA)") (class "Default")
      (node (ref "LED9") (pin "A") (pinfunction "A_A") (pintype "passive"))
      (node (ref "R14") (pin "2") (pinfunction "2_2") (pintype "passive"))
    )
    (net (code "42") (name "Net-(LED10-PadA)") (class "Default")
      (node (ref "LED10") (pin "A") (pinfunction "A_A") (pintype "passive"))
      (node (ref "R15") (pin "2") (pinfunction "2_2") (pintype "passive"))
    )
    (net (code "43") (name "Net-(R16-Pad2)") (class "Default")
      (node (ref "R16") (pin "2") (pinfunction "2_2") (pintype "passive"))
      (node (ref "SG1") (pin "+") (pinfunction "+_+") (pintype "passive"))
    )
    (net (code "44") (name "Net-(T1-B)") (class "Default")
      (node (ref "R1") (pin "2") (pinfunction "2_2") (pintype "passive"))
      (node (ref "T1") (pin "1") (pinfunction "B_1") (pintype "passive"))
    )
    (net (code "45") (name "Net-(T1-C)") (class "Default")
      (node (ref "R6") (pin "2") (pinfunction "2_2") (pintype "passive"))
      (node (ref "T1") (pin "2") (pinfunction "C_2") (pintype "passive"))
    )
    (net (code "46") (name "Net-(T2-B)") (class "Default")
      (node (ref "R2") (pin "2") (pinfunction "2_2") (pintype "passive"))
      (node (ref "T2") (pin "1") (pinfunction "B_1") (pintype "passive"))
    )
    (net (code "47") (name "Net-(T2-C)") (class "Default")
      (node (ref "R7") (pin "2") (pinfunction "2_2") (pintype "passive"))
      (node (ref "T2") (pin "2") (pinfunction "C_2") (pintype "passive"))
    )
    (net (code "48") (name "Net-(T3-B)") (class "Default")
      (node (ref "R3") (pin "2") (pinfunction "2_2") (pintype "passive"))
      (node (ref "T3") (pin "1") (pinfunction "B_1") (pintype "passive"))
    )
    (net (code "49") (name "Net-(T3-C)") (class "Default")
      (node (ref "R8") (pin "2") (pinfunction "2_2") (pintype "passive"))
      (node (ref "T3") (pin "2") (pinfunction "C_2") (pintype "passive"))
    )
    (net (code "50") (name "Net-(T4-B)") (class "Default")
      (node (ref "R4") (pin "2") (pinfunction "2_2") (pintype "passive"))
      (node (ref "T4") (pin "1") (pinfunction "B_1") (pintype "passive"))
    )
    (net (code "51") (name "Net-(T4-C)") (class "Default")
      (node (ref "R9") (pin "2") (pinfunction "2_2") (pintype "passive"))
      (node (ref "T4") (pin "2") (pinfunction "C_2") (pintype "passive"))
    )
    (net (code "52") (name "Net-(T5-B)") (class "Default")
      (node (ref "R5") (pin "2") (pinfunction "2_2") (pintype "passive"))
      (node (ref "T5") (pin "1") (pinfunction "B_1") (pintype "passive"))
    )
    (net (code "53") (name "Net-(T5-C)") (class "Default")
      (node (ref "R10") (pin "2") (pinfunction "2_2") (pintype "passive"))
      (node (ref "T5") (pin "2") (pinfunction "C_2") (pintype "passive"))
    )
    (net (code "54") (name "Net-(T6A-B)") (class "Default")
      (node (ref "R17") (pin "2") (pinfunction "2_2") (pintype "passive"))
      (node (ref "T6") (pin "4") (pinfunction "B_4") (pintype "passive"))
    )
    (net (code "55") (name "Net-(T6B-B)") (class "Default")
      (node (ref "R26") (pin "1") (pinfunction "1_1") (pintype "passive"))
      (node (ref "T6") (pin "2") (pinfunction "B_2") (pintype "passive"))
    )
    (net (code "56") (name "Net-(U$1-D+)") (class "Default")
      (node (ref "J3") (pin "D+") (pinfunction "D+_D+") (pintype "bidirectional"))
      (node (ref "U$1") (pin "5") (pinfunction "D+_5") (pintype "bidirectional"))
    )
    (net (code "57") (name "Net-(U$1-D-)") (class "Default")
      (node (ref "J3") (pin "D-") (pinfunction "D-_D-") (pintype "bidirectional"))
      (node (ref "U$1") (pin "6") (pinfunction "D-_6") (pintype "bidirectional"))
    )
    (net (code "58") (name "O2-CONC") (class "Default")
      (node (ref "SL1") (pin "5") (pinfunction "5_5") (pintype "passive"))
      (node (ref "SV1") (pin "14") (pinfunction "14_14") (pintype "passive"))
      (node (ref "U1") (pin "4") (pinfunction "SENSOR_VP_4") (pintype "input"))
    )
    (net (code "59") (name "RL1") (class "Default")
      (node (ref "R1") (pin "1") (pinfunction "1_1") (pintype "passive"))
      (node (ref "SV1") (pin "22") (pinfunction "22_22") (pintype "passive"))
      (node (ref "U1") (pin "8") (pinfunction "I032_8") (pintype "bidirectional"))
    )
    (net (code "60") (name "RL2") (class "Default")
      (node (ref "R2") (pin "1") (pinfunction "1_1") (pintype "passive"))
      (node (ref "SV1") (pin "24") (pinfunction "24_24") (pintype "passive"))
      (node (ref "U1") (pin "9") (pinfunction "I033_9") (pintype "bidirectional"))
    )
    (net (code "61") (name "RL3") (class "Default")
      (node (ref "R3") (pin "1") (pinfunction "1_1") (pintype "passive"))
      (node (ref "SV1") (pin "26") (pinfunction "26_26") (pintype "passive"))
      (node (ref "U1") (pin "10") (pinfunction "I025_10") (pintype "bidirectional"))
    )
    (net (code "62") (name "RL4") (class "Default")
      (node (ref "R4") (pin "1") (pinfunction "1_1") (pintype "passive"))
      (node (ref "SV1") (pin "28") (pinfunction "28_28") (pintype "passive"))
      (node (ref "U1") (pin "11") (pinfunction "I026_11") (pintype "bidirectional"))
    )
    (net (code "63") (name "RL5") (class "Default")
      (node (ref "R5") (pin "1") (pinfunction "1_1") (pintype "passive"))
      (node (ref "SV1") (pin "30") (pinfunction "30_30") (pintype "passive"))
      (node (ref "U1") (pin "12") (pinfunction "IO27_12") (pintype "bidirectional"))
    )
    (net (code "64") (name "RST0") (class "Default")
      (node (ref "2.2\"TFT") (pin "6") (pinfunction "6_6") (pintype "bidirectional"))
      (node (ref "U1") (pin "26") (pinfunction "IO4_26") (pintype "bidirectional"))
    )
    (net (code "65") (name "RTS") (class "Default")
      (node (ref "R26") (pin "2") (pinfunction "2_2") (pintype "passive"))
      (node (ref "T6") (pin "3") (pinfunction "E_3") (pintype "passive"))
      (node (ref "U$1") (pin "14") (pinfunction "RTS_14") (pintype "bidirectional"))
    )
    (net (code "66") (name "RX0") (class "Default")
      (node (ref "SV1") (pin "12") (pinfunction "12_12") (pintype "passive"))
      (node (ref "U$1") (pin "2") (pinfunction "TX_2") (pintype "bidirectional"))
      (node (ref "U1") (pin "34") (pinfunction "RXD0_34") (pintype "bidirectional"))
    )
    (net (code "67") (name "RX1") (class "Default")
      (node (ref "SV1") (pin "11") (pinfunction "11_11") (pintype "passive"))
      (node (ref "U1") (pin "27") (pinfunction "IO16_27") (pintype "bidirectional"))
      (node (ref "UART") (pin "2") (pinfunction "2_2") (pintype "passive"))
    )
    (net (code "68") (name "SCL") (class "Default")
      (node (ref "J1") (pin "4") (pinfunction "4_4") (pintype "passive"))
      (node (ref "J4") (pin "4") (pinfunction "4_4") (pintype "passive"))
      (node (ref "OXY-SENSE") (pin "3") (pinfunction "3_3") (pintype "passive"))
      (node (ref "SV1") (pin "18") (pinfunction "18_18") (pintype "passive"))
      (node (ref "U$4") (pin "3") (pinfunction "SCL_3") (pintype "bidirectional"))
      (node (ref "U1") (pin "36") (pinfunction "IO22_36") (pintype "bidirectional"))
    )
    (net (code "69") (name "SDA") (class "Default")
      (node (ref "J1") (pin "3") (pinfunction "3_3") (pintype "passive"))
      (node (ref "J4") (pin "3") (pinfunction "3_3") (pintype "passive"))
      (node (ref "OXY-SENSE") (pin "4") (pinfunction "4_4") (pintype "passive"))
      (node (ref "SV1") (pin "20") (pinfunction "20_20") (pintype "passive"))
      (node (ref "U$4") (pin "4") (pinfunction "SDA_4") (pintype "bidirectional"))
      (node (ref "U1") (pin "33") (pinfunction "IO21_33") (pintype "bidirectional"))
    )
    (net (code "70") (name "TEMP1") (class "Default")
      (node (ref "R20") (pin "2") (pinfunction "2_2") (pintype "passive"))
      (node (ref "R23") (pin "2") (pinfunction "2_2") (pintype "passive"))
      (node (ref "U1") (pin "6") (pinfunction "I034_6") (pintype "input"))
    )
    (net (code "71") (name "TEMP2") (class "Default")
      (node (ref "R22") (pin "2") (pinfunction "2_2") (pintype "passive"))
      (node (ref "R24") (pin "2") (pinfunction "2_2") (pintype "passive"))
      (node (ref "U1") (pin "7") (pinfunction "I035_7") (pintype "input"))
    )
    (net (code "72") (name "TX0") (class "Default")
      (node (ref "SV1") (pin "10") (pinfunction "10_10") (pintype "passive"))
      (node (ref "U$1") (pin "3") (pinfunction "RX_3") (pintype "bidirectional"))
      (node (ref "U1") (pin "35") (pinfunction "TXD0_35") (pintype "bidirectional"))
    )
    (net (code "73") (name "TX1") (class "Default")
      (node (ref "SV1") (pin "9") (pinfunction "9_9") (pintype "passive"))
      (node (ref "U1") (pin "28") (pinfunction "IO17_28") (pintype "bidirectional"))
      (node (ref "UART") (pin "3") (pinfunction "3_3") (pintype "passive"))
    )
    (net (code "74") (name "unconnected-(J3-PadID)") (class "Default")
      (node (ref "J3") (pin "ID") (pinfunction "ID_ID") (pintype "bidirectional"))
    )
    (net (code "75") (name "unconnected-(SL1-Pad3)") (class "Default")
      (node (ref "SL1") (pin "3") (pinfunction "3_3") (pintype "passive"))
    )
    (net (code "76") (name "unconnected-(T1-C{slash}-Pad2@1)") (class "Default")
      (node (ref "T1") (pin "2@1") (pinfunction "C/_2@1") (pintype "passive"))
    )
    (net (code "77") (name "unconnected-(T2-C{slash}-Pad2@1)") (class "Default")
      (node (ref "T2") (pin "2@1") (pinfunction "C/_2@1") (pintype "passive"))
    )
    (net (code "78") (name "unconnected-(T3-C{slash}-Pad2@1)") (class "Default")
      (node (ref "T3") (pin "2@1") (pinfunction "C/_2@1") (pintype "passive"))
    )
    (net (code "79") (name "unconnected-(T4-C{slash}-Pad2@1)") (class "Default")
      (node (ref "T4") (pin "2@1") (pinfunction "C/_2@1") (pintype "passive"))
    )
    (net (code "80") (name "unconnected-(T5-C{slash}-Pad2@1)") (class "Default")
      (node (ref "T5") (pin "2@1") (pinfunction "C/_2@1") (pintype "passive"))
    )
    (net (code "81") (name "unconnected-(U$1-CTS-Pad9)") (class "Default")
      (node (ref "U$1") (pin "9") (pinfunction "CTS_9") (pintype "bidirectional"))
    )
    (net (code "82") (name "unconnected-(U$1-DCD-Pad12)") (class "Default")
      (node (ref "U$1") (pin "12") (pinfunction "DCD_12") (pintype "bidirectional"))
    )
    (net (code "83") (name "unconnected-(U$1-DSR-Pad10)") (class "Default")
      (node (ref "U$1") (pin "10") (pinfunction "DSR_10") (pintype "bidirectional"))
    )
    (net (code "84") (name "unconnected-(U$1-RI-Pad11)") (class "Default")
      (node (ref "U$1") (pin "11") (pinfunction "RI_11") (pintype "bidirectional"))
    )
    (net (code "85") (name "unconnected-(U$1-RS232-Pad15)") (class "Default")
      (node (ref "U$1") (pin "15") (pinfunction "RS232_15") (pintype "bidirectional"))
    )
    (net (code "86") (name "unconnected-(U$1-XI-Pad7)") (class "Default")
      (node (ref "U$1") (pin "7") (pinfunction "XI_7") (pintype "bidirectional"))
    )
    (net (code "87") (name "unconnected-(U$1-XO-Pad8)") (class "Default")
      (node (ref "U$1") (pin "8") (pinfunction "XO_8") (pintype "bidirectional"))
    )
    (net (code "88") (name "unconnected-(U1-SCL{slash}CLK-Pad20)") (class "Default")
      (node (ref "U1") (pin "20") (pinfunction "SCL/CLK_20") (pintype "bidirectional"))
    )
    (net (code "89") (name "unconnected-(U1-SCS{slash}CMD-Pad19)") (class "Default")
      (node (ref "U1") (pin "19") (pinfunction "SCS/CMD_19") (pintype "bidirectional"))
    )
    (net (code "90") (name "unconnected-(U1-SD1{slash}SD1-Pad22)") (class "Default")
      (node (ref "U1") (pin "22") (pinfunction "SD1/SD1_22") (pintype "bidirectional"))
    )
    (net (code "91") (name "unconnected-(U1-SDO{slash}SD0-Pad21)") (class "Default")
      (node (ref "U1") (pin "21") (pinfunction "SDO/SD0_21") (pintype "bidirectional"))
    )
    (net (code "92") (name "unconnected-(U1-SHD{slash}SD2-Pad17)") (class "Default")
      (node (ref "U1") (pin "17") (pinfunction "SHD/SD2_17") (pintype "bidirectional"))
    )
    (net (code "93") (name "unconnected-(U1-SWP{slash}SD3-Pad18)") (class "Default")
      (node (ref "U1") (pin "18") (pinfunction "SWP/SD3_18") (pintype "bidirectional"))
    )
  )
)
